# SD_Card.net
KiCad netlist of a schematic drawn in Altium Designer
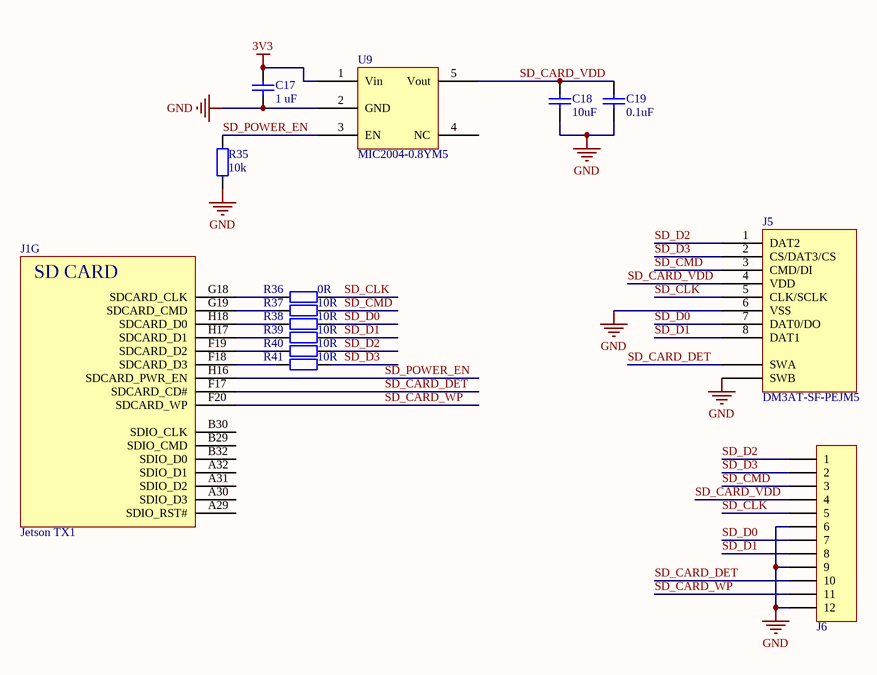
[diagram p0: SD_Card.SchDoc]

(export (version "E")
  (design (tool "Eeschema 10.0.6"))
  (components
    (comp (ref "C17")
      (value "GRM188R61A105KA61D")
      (footprint "0603C_M")
      (description "CAP CER 1UF 10V X5R 0603")
      (fields
        (field (name "MANUFACTURER") "Murata")
        (field (name "TOLERANCE") "10 %")
        (field (name "CAPACITANCE") "1 uF")
      )
      (libsource (lib "KMTI-main") (part "GRM188R61A105KA61D"))
    )
    (comp (ref "C18")
      (value "10uF")
      (footprint "0603C_M")
      (description "CAP CER 10UF 6.3V X5R 0603")
      (fields
        (field (name "MANUFACTURER") "Murata Electronics North America")
        (field (name "MANUFACTURER PART NUMBER") "GRM188R60J106ME47D")
      )
      (libsource (lib "KMTI-main") (part "GRM188R60J106ME47D"))
    )
    (comp (ref "C19")
      (value "GRM155R71C104KA88D")
      (footprint "0402C_M")
      (description "CAP CER 0.1UF 16V X7R 0402")
      (fields
        (field (name "MANUFACTURER") "Murata Electronics North America")
        (field (name "TOLERANCE") "±10%")
        (field (name "CAPACITANCE") "0.1uF")
      )
      (libsource (lib "KMTI-main") (part "GRM155R71C104KA88D"))
    )
    (comp (ref "J1")
      (value "Jetson TX1")
      (footprint "Nvidia Jetson TX1")
      (description "Nvidia computing module")
      (libsource (lib "Modules") (part "NVIDIA_Jetson_TX1"))
    )
    (comp (ref "J5")
      (value "DM3AT-SF-PEJM5")
      (footprint "DM3AT-SF-PEJM5")
      (description "CONN MICRO SD CARD PUSH-PUSH R/A")
      (fields (field (name "MANUFACTURER") "Hirose Electric (HRS)"))
      (libsource (lib "KMTI-main") (part "DM3AT-SF-PEJM5"))
    )
    (comp (ref "J6")
      (value "0527451297")
      (footprint "52745-1297")
      (description "CONN FFC TOP 12POS 0.50MM R/A")
      (fields (field (name "MANUFACTURER") "Molex, LLC"))
      (libsource (lib "KMTI-main") (part "0527451297"))
    )
    (comp (ref "R35")
      (value "10k")
      (footprint "0402R_M")
      (description "RES SMD 10K OHM 1% 1/16W 0402")
      (fields
        (field (name "MANUFACTURER") "Vishay Dale")
        (field (name "MANUFACTURER PART NUMBER") "CRCW040210K0FKED")
      )
      (libsource (lib "KMTI-main") (part "CRCW040210K0FKED"))
    )
    (comp (ref "R36")
      (value "0R")
      (footprint "0402R_M")
      (fields (field (name "Comment") "Generic resitor"))
      (libsource (lib "KMTI-main") (part "Resistor"))
    )
    (comp (ref "R37")
      (value "10R")
      (footprint "0402R_M")
      (description "RES SMD 10 OHM 1% 1/16W 0402")
      (fields
        (field (name "MANUFACTURER") "Vishay Dale")
        (field (name "MANUFACTURER PART NUMBER") "CRCW040210R0FKED")
      )
      (libsource (lib "KMTI-main") (part "CRCW040210R0FKED"))
    )
    (comp (ref "R38")
      (value "10R")
      (footprint "0402R_M")
      (description "RES SMD 10 OHM 1% 1/16W 0402")
      (fields
        (field (name "MANUFACTURER") "Vishay Dale")
        (field (name "MANUFACTURER PART NUMBER") "CRCW040210R0FKED")
      )
      (libsource (lib "KMTI-main") (part "CRCW040210R0FKED"))
    )
    (comp (ref "R39")
      (value "10R")
      (footprint "0402R_M")
      (description "RES SMD 10 OHM 1% 1/16W 0402")
      (fields
        (field (name "MANUFACTURER") "Vishay Dale")
        (field (name "MANUFACTURER PART NUMBER") "CRCW040210R0FKED")
      )
      (libsource (lib "KMTI-main") (part "CRCW040210R0FKED"))
    )
    (comp (ref "R40")
      (value "10R")
      (footprint "0402R_M")
      (description "RES SMD 10 OHM 1% 1/16W 0402")
      (fields
        (field (name "MANUFACTURER") "Vishay Dale")
        (field (name "MANUFACTURER PART NUMBER") "CRCW040210R0FKED")
      )
      (libsource (lib "KMTI-main") (part "CRCW040210R0FKED"))
    )
    (comp (ref "R41")
      (value "10R")
      (footprint "0402R_M")
      (description "RES SMD 10 OHM 1% 1/16W 0402")
      (fields
        (field (name "MANUFACTURER") "Vishay Dale")
        (field (name "MANUFACTURER PART NUMBER") "CRCW040210R0FKED")
      )
      (libsource (lib "KMTI-main") (part "CRCW040210R0FKED"))
    )
    (comp (ref "U9")
      (value "MIC2004-0.8YM5")
      (footprint "SOT23_M5_M")
      (description "IC DISTRIBUTION SW 0.8A SOT23-5")
      (fields (field (name "MANUFACTURER") "Microchip Technology"))
      (libsource (lib "KMTI-main") (part "MIC2004-0.8YM5"))
    )
  )
  (nets
    (net (code "1") (name "/SD_CARD_DET") (class "Default")
      (node (ref "J1") (pin "F17") (pinfunction "SDCARD_CD#_F17") (pintype "passive"))
      (node (ref "J5") (pin "SWA") (pinfunction "SWA_SWA") (pintype "passive"))
      (node (ref "J6") (pin "10") (pinfunction "10_10") (pintype "passive"))
    )
    (net (code "2") (name "/SD_CARD_VDD") (class "Default")
      (node (ref "C18") (pin "2") (pinfunction "2_2") (pintype "passive"))
      (node (ref "C19") (pin "2") (pinfunction "2_2") (pintype "passive"))
      (node (ref "J5") (pin "4") (pinfunction "VDD_4") (pintype "passive"))
      (node (ref "J6") (pin "4") (pinfunction "4_4") (pintype "passive"))
      (node (ref "U9") (pin "5") (pinfunction "Vout_5") (pintype "passive"))
    )
    (net (code "3") (name "/SD_CARD_WP") (class "Default")
      (node (ref "J1") (pin "F20") (pinfunction "SDCARD_WP_F20") (pintype "passive"))
      (node (ref "J6") (pin "11") (pinfunction "11_11") (pintype "passive"))
    )
    (net (code "4") (name "/SD_CLK") (class "Default")
      (node (ref "J5") (pin "5") (pinfunction "CLK/SCLK_5") (pintype "passive"))
      (node (ref "J6") (pin "5") (pinfunction "5_5") (pintype "passive"))
      (node (ref "R36") (pin "2") (pinfunction "2_2") (pintype "passive"))
    )
    (net (code "5") (name "/SD_CMD") (class "Default")
      (node (ref "J5") (pin "3") (pinfunction "CMD/DI_3") (pintype "passive"))
      (node (ref "J6") (pin "3") (pinfunction "3_3") (pintype "passive"))
      (node (ref "R37") (pin "2") (pinfunction "2_2") (pintype "passive"))
    )
    (net (code "6") (name "/SD_D0") (class "Default")
      (node (ref "J5") (pin "7") (pinfunction "DAT0/DO_7") (pintype "passive"))
      (node (ref "J6") (pin "7") (pinfunction "7_7") (pintype "passive"))
      (node (ref "R38") (pin "2") (pinfunction "2_2") (pintype "passive"))
    )
    (net (code "7") (name "/SD_D1") (class "Default")
      (node (ref "J5") (pin "8") (pinfunction "DAT1_8") (pintype "passive"))
      (node (ref "J6") (pin "8") (pinfunction "8_8") (pintype "passive"))
      (node (ref "R39") (pin "2") (pinfunction "2_2") (pintype "passive"))
    )
    (net (code "8") (name "/SD_D2") (class "Default")
      (node (ref "J5") (pin "1") (pinfunction "DAT2_1") (pintype "passive"))
      (node (ref "J6") (pin "1") (pinfunction "1_1") (pintype "passive"))
      (node (ref "R40") (pin "2") (pinfunction "2_2") (pintype "passive"))
    )
    (net (code "9") (name "/SD_D3") (class "Default")
      (node (ref "J5") (pin "2") (pinfunction "CS/DAT3/CS_2") (pintype "passive"))
      (node (ref "J6") (pin "2") (pinfunction "2_2") (pintype "passive"))
      (node (ref "R41") (pin "2") (pinfunction "2_2") (pintype "passive"))
    )
    (net (code "10") (name "/SD_POWER_EN") (class "Default")
      (node (ref "J1") (pin "H16") (pinfunction "SDCARD_PWR_EN_H16") (pintype "passive"))
      (node (ref "R35") (pin "2") (pinfunction "2_2") (pintype "passive"))
      (node (ref "U9") (pin "3") (pinfunction "EN_3") (pintype "passive"))
    )
    (net (code "11") (name "3V3") (class "Default")
      (node (ref "C17") (pin "2") (pinfunction "2_2") (pintype "passive"))
      (node (ref "U9") (pin "1") (pinfunction "Vin_1") (pintype "passive"))
    )
    (net (code "12") (name "GND") (class "Default")
      (node (ref "C17") (pin "1") (pinfunction "1_1") (pintype "passive"))
      (node (ref "C18") (pin "1") (pinfunction "1_1") (pintype "passive"))
      (node (ref "C19") (pin "1") (pinfunction "1_1") (pintype "passive"))
      (node (ref "J5") (pin "6") (pinfunction "VSS_6") (pintype "passive"))
      (node (ref "J5") (pin "SWB") (pinfunction "SWB_SWB") (pintype "passive"))
      (node (ref "J6") (pin "12") (pinfunction "12_12") (pintype "passive"))
      (node (ref "J6") (pin "6") (pinfunction "6_6") (pintype "passive"))
      (node (ref "J6") (pin "9") (pinfunction "9_9") (pintype "passive"))
      (node (ref "R35") (pin "1") (pinfunction "1_1") (pintype "passive"))
      (node (ref "U9") (pin "2") (pinfunction "GND_2") (pintype "passive"))
    )
    (net (code "13") (name "Net-(J1G-SDCARD_CLK)") (class "Default")
      (node (ref "J1") (pin "G18") (pinfunction "SDCARD_CLK_G18") (pintype "passive"))
      (node (ref "R36") (pin "1") (pinfunction "1_1") (pintype "passive"))
    )
    (net (code "14") (name "Net-(J1G-SDCARD_CMD)") (class "Default")
      (node (ref "J1") (pin "G19") (pinfunction "SDCARD_CMD_G19") (pintype "passive"))
      (node (ref "R37") (pin "1") (pinfunction "1_1") (pintype "passive"))
    )
    (net (code "15") (name "Net-(J1G-SDCARD_D0)") (class "Default")
      (node (ref "J1") (pin "H18") (pinfunction "SDCARD_D0_H18") (pintype "passive"))
      (node (ref "R38") (pin "1") (pinfunction "1_1") (pintype "passive"))
    )
    (net (code "16") (name "Net-(J1G-SDCARD_D1)") (class "Default")
      (node (ref "J1") (pin "H17") (pinfunction "SDCARD_D1_H17") (pintype "passive"))
      (node (ref "R39") (pin "1") (pinfunction "1_1") (pintype "passive"))
    )
    (net (code "17") (name "Net-(J1G-SDCARD_D2)") (class "Default")
      (node (ref "J1") (pin "F19") (pinfunction "SDCARD_D2_F19") (pintype "passive"))
      (node (ref "R40") (pin "1") (pinfunction "1_1") (pintype "passive"))
    )
    (net (code "18") (name "Net-(J1G-SDCARD_D3)") (class "Default")
      (node (ref "J1") (pin "F18") (pinfunction "SDCARD_D3_F18") (pintype "passive"))
      (node (ref "R41") (pin "1") (pinfunction "1_1") (pintype "passive"))
    )
    (net (code "19") (name "unconnected-(J1G-SDIO_CLK-PadB30)") (class "Default")
      (node (ref "J1") (pin "B30") (pinfunction "SDIO_CLK_B30") (pintype "passive"))
    )
    (net (code "20") (name "unconnected-(J1G-SDIO_CMD-PadB29)") (class "Default")
      (node (ref "J1") (pin "B29") (pinfunction "SDIO_CMD_B29") (pintype "passive"))
    )
    (net (code "21") (name "unconnected-(J1G-SDIO_D0-PadB32)") (class "Default")
      (node (ref "J1") (pin "B32") (pinfunction "SDIO_D0_B32") (pintype "passive"))
    )
    (net (code "22") (name "unconnected-(J1G-SDIO_D1-PadA32)") (class "Default")
      (node (ref "J1") (pin "A32") (pinfunction "SDIO_D1_A32") (pintype "passive"))
    )
    (net (code "23") (name "unconnected-(J1G-SDIO_D2-PadA31)") (class "Default")
      (node (ref "J1") (pin "A31") (pinfunction "SDIO_D2_A31") (pintype "passive"))
    )
    (net (code "24") (name "unconnected-(J1G-SDIO_D3-PadA30)") (class "Default")
      (node (ref "J1") (pin "A30") (pinfunction "SDIO_D3_A30") (pintype "passive"))
    )
    (net (code "25") (name "unconnected-(J1G-SDIO_RST#-PadA29)") (class "Default")
      (node (ref "J1") (pin "A29") (pinfunction "SDIO_RST#_A29") (pintype "passive"))
    )
    (net (code "26") (name "unconnected-(U9-NC-Pad4)") (class "Default")
      (node (ref "U9") (pin "4") (pinfunction "NC_4") (pintype "passive"))
    )
  )
)
